# sumoboard.net
KiCad netlist of a schematic drawn in EAGLE
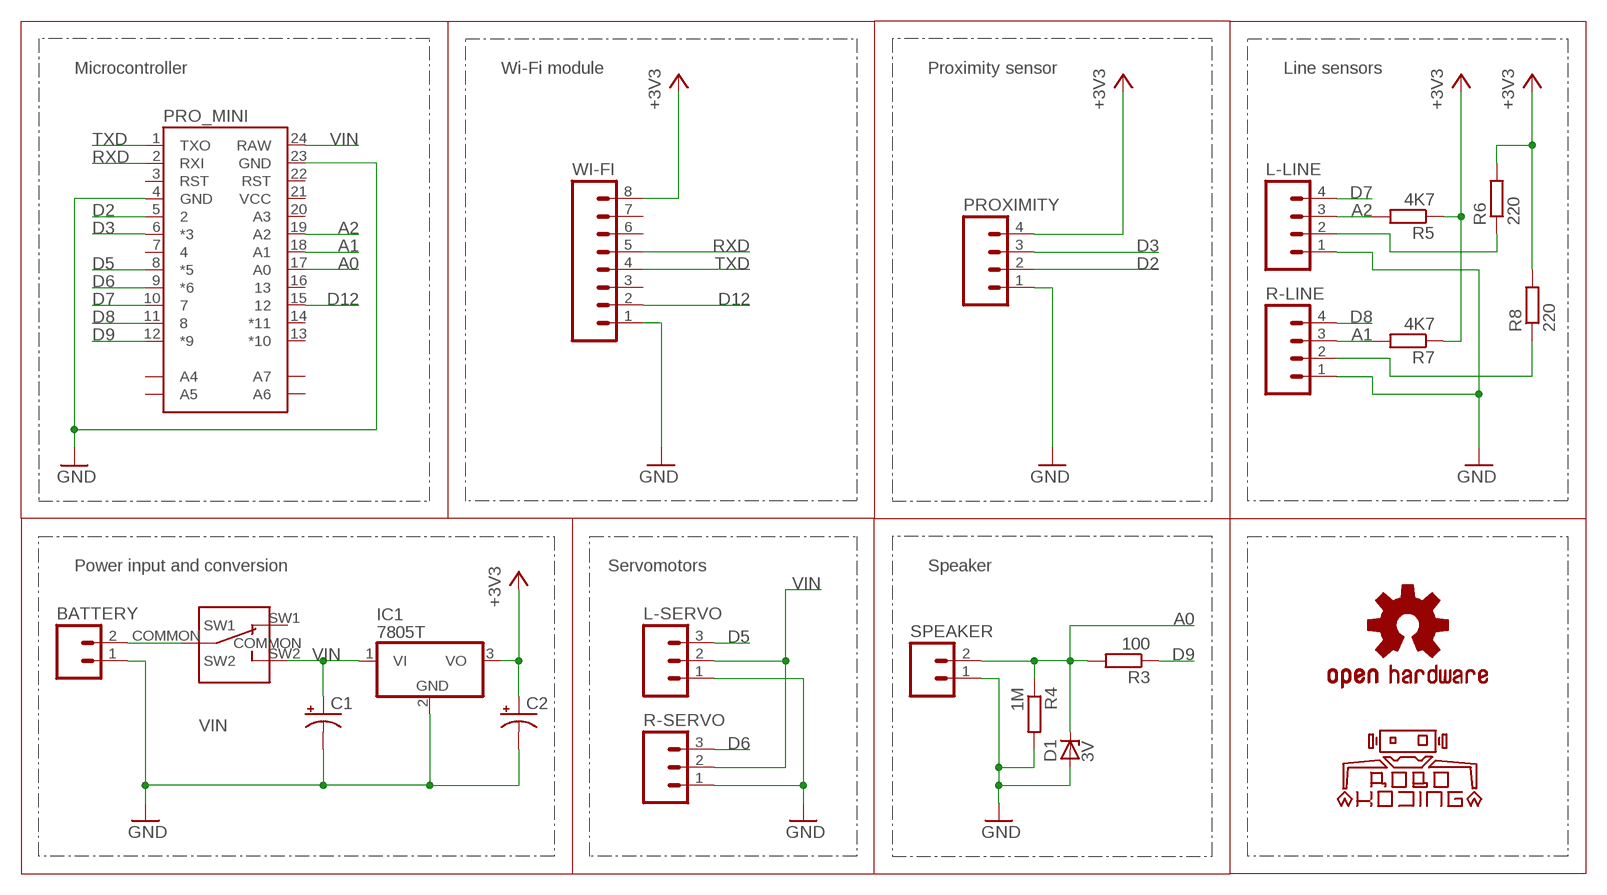
[diagram p0: schematic, sheet 1]

(export (version "E")
  (design (tool "Eeschema 10.0.6"))
  (components
    (comp (ref "BATTERY")
      (value "M02LOCK_LONGPADS")
      (footprint "eagle-import:1X02_LOCK_LONGPADS")
      (libsource (lib "eagle-import") (part "M02LOCK_LONGPADS"))
    )
    (comp (ref "C1")
      (value "CPOL-USE5-10.5")
      (footprint "eagle-import:E5-10,5")
      (libsource (lib "eagle-import") (part "CPOL-USE5-10.5"))
    )
    (comp (ref "C2")
      (value "CPOL-USE5-10.5")
      (footprint "eagle-import:E5-10,5")
      (libsource (lib "eagle-import") (part "CPOL-USE5-10.5"))
    )
    (comp (ref "D1")
      (value "3V")
      (footprint "eagle-import:DO35Z10")
      (libsource (lib "eagle-import") (part "1N821"))
    )
    (comp (ref "IC1")
      (value "7805T")
      (footprint "eagle-import:TO220H")
      (libsource (lib "eagle-import") (part "78T05"))
    )
    (comp (ref "L-LINE")
      (value "M04LOCK_LONGPADS")
      (footprint "eagle-import:1X04_LOCK_LONGPADS")
      (libsource (lib "eagle-import") (part "M04LOCK_LONGPADS"))
    )
    (comp (ref "L-SERVO")
      (value "M03LOCK_LONGPADS")
      (footprint "eagle-import:1X03_LOCK_LONGPADS")
      (libsource (lib "eagle-import") (part "M03LOCK_LONGPADS"))
    )
    (comp (ref "LOGO1")
      (value "OSHW-LOGOM")
      (footprint "eagle-import:OSHW-LOGO-M")
      (libsource (lib "eagle-import") (part "OSHW-LOGOM"))
    )
    (comp (ref "LOGO2")
      (value "ROBOKODING-LOGOM")
      (footprint "eagle-import:ROBOKODING-LOGO-M")
      (libsource (lib "eagle-import") (part "ROBOKODING-LOGOM"))
    )
    (comp (ref "POWER")
      (value "SPDT_SLIDE_SWITCH")
      (footprint "eagle-import:SPDT_SLIDE_SWITCH")
      (libsource (lib "eagle-import") (part "SPDT_SLIDE_SWITCH"))
    )
    (comp (ref "PROXIMITY")
      (value "M04LOCK_LONGPADS")
      (footprint "eagle-import:1X04_LOCK_LONGPADS")
      (libsource (lib "eagle-import") (part "M04LOCK_LONGPADS"))
    )
    (comp (ref "PRO_MINI")
      (value "ARDUINO_PRO_MINI")
      (footprint "eagle-import:ARDUINO_PRO_MINI")
      (libsource (lib "eagle-import") (part "ARDUINO_PRO_MINI"))
    )
    (comp (ref "R-LINE")
      (value "M04LOCK_LONGPADS")
      (footprint "eagle-import:1X04_LOCK_LONGPADS")
      (libsource (lib "eagle-import") (part "M04LOCK_LONGPADS"))
    )
    (comp (ref "R-SERVO")
      (value "M03LOCK_LONGPADS")
      (footprint "eagle-import:1X03_LOCK_LONGPADS")
      (libsource (lib "eagle-import") (part "M03LOCK_LONGPADS"))
    )
    (comp (ref "R3")
      (value "100")
      (footprint "eagle-import:0204_5")
      (libsource (lib "eagle-import") (part "R-EU_0204/5"))
    )
    (comp (ref "R4")
      (value "1M")
      (footprint "eagle-import:0204_5")
      (libsource (lib "eagle-import") (part "R-EU_0204/5"))
    )
    (comp (ref "R5")
      (value "4K7")
      (footprint "eagle-import:0204_5")
      (libsource (lib "eagle-import") (part "R-EU_0204/5"))
    )
    (comp (ref "R6")
      (value "220")
      (footprint "eagle-import:0204_5")
      (libsource (lib "eagle-import") (part "R-EU_0204/5"))
    )
    (comp (ref "R7")
      (value "4K7")
      (footprint "eagle-import:0204_5")
      (libsource (lib "eagle-import") (part "R-EU_0204/5"))
    )
    (comp (ref "R8")
      (value "220")
      (footprint "eagle-import:0204_5")
      (libsource (lib "eagle-import") (part "R-EU_0204/5"))
    )
    (comp (ref "SPEAKER")
      (value "M02LOCK_LONGPADS")
      (footprint "eagle-import:1X02_LOCK_LONGPADS")
      (libsource (lib "eagle-import") (part "M02LOCK_LONGPADS"))
    )
    (comp (ref "WI-FI")
      (value "M08LOCK_LONGPADS")
      (footprint "eagle-import:1X08_LOCK_LONGPADS")
      (libsource (lib "eagle-import") (part "M08LOCK_LONGPADS"))
    )
  )
  (nets
    (net (code "1") (name "+3V3") (class "Default")
      (node (ref "C2") (pin "+") (pinfunction "+_+") (pintype "passive"))
      (node (ref "IC1") (pin "3") (pinfunction "VO_3") (pintype "passive"))
      (node (ref "PROXIMITY") (pin "4") (pinfunction "4_4") (pintype "passive"))
      (node (ref "R5") (pin "1") (pinfunction "1_1") (pintype "passive"))
      (node (ref "R6") (pin "2") (pinfunction "2_2") (pintype "passive"))
      (node (ref "R7") (pin "1") (pinfunction "1_1") (pintype "passive"))
      (node (ref "R8") (pin "2") (pinfunction "2_2") (pintype "passive"))
      (node (ref "WI-FI") (pin "8") (pinfunction "8_8") (pintype "passive"))
    )
    (net (code "2") (name "/A0") (class "Default")
      (node (ref "D1") (pin "C") (pinfunction "C_C") (pintype "passive"))
      (node (ref "PRO_MINI") (pin "17") (pinfunction "A0_17") (pintype "bidirectional"))
      (node (ref "R3") (pin "2") (pinfunction "2_2") (pintype "passive"))
      (node (ref "R4") (pin "1") (pinfunction "1_1") (pintype "passive"))
      (node (ref "SPEAKER") (pin "2") (pinfunction "2_2") (pintype "passive"))
    )
    (net (code "3") (name "/A1") (class "Default")
      (node (ref "PRO_MINI") (pin "18") (pinfunction "A1_18") (pintype "bidirectional"))
      (node (ref "R-LINE") (pin "3") (pinfunction "3_3") (pintype "passive"))
      (node (ref "R7") (pin "2") (pinfunction "2_2") (pintype "passive"))
    )
    (net (code "4") (name "/A2") (class "Default")
      (node (ref "L-LINE") (pin "3") (pinfunction "3_3") (pintype "passive"))
      (node (ref "PRO_MINI") (pin "19") (pinfunction "A2_19") (pintype "bidirectional"))
      (node (ref "R5") (pin "2") (pinfunction "2_2") (pintype "passive"))
    )
    (net (code "5") (name "/D2") (class "Default")
      (node (ref "PROXIMITY") (pin "2") (pinfunction "2_2") (pintype "passive"))
      (node (ref "PRO_MINI") (pin "5") (pinfunction "2_5") (pintype "bidirectional"))
    )
    (net (code "6") (name "/D3") (class "Default")
      (node (ref "PROXIMITY") (pin "3") (pinfunction "3_3") (pintype "passive"))
      (node (ref "PRO_MINI") (pin "6") (pinfunction "*3_6") (pintype "bidirectional"))
    )
    (net (code "7") (name "/D5") (class "Default")
      (node (ref "L-SERVO") (pin "3") (pinfunction "3_3") (pintype "passive"))
      (node (ref "PRO_MINI") (pin "8") (pinfunction "*5_8") (pintype "bidirectional"))
    )
    (net (code "8") (name "/D6") (class "Default")
      (node (ref "PRO_MINI") (pin "9") (pinfunction "*6_9") (pintype "bidirectional"))
      (node (ref "R-SERVO") (pin "3") (pinfunction "3_3") (pintype "passive"))
    )
    (net (code "9") (name "/D7") (class "Default")
      (node (ref "L-LINE") (pin "4") (pinfunction "4_4") (pintype "passive"))
      (node (ref "PRO_MINI") (pin "10") (pinfunction "7_10") (pintype "bidirectional"))
    )
    (net (code "10") (name "/D8") (class "Default")
      (node (ref "PRO_MINI") (pin "11") (pinfunction "8_11") (pintype "bidirectional"))
      (node (ref "R-LINE") (pin "4") (pinfunction "4_4") (pintype "passive"))
    )
    (net (code "11") (name "/D9") (class "Default")
      (node (ref "PRO_MINI") (pin "12") (pinfunction "*9_12") (pintype "bidirectional"))
      (node (ref "R3") (pin "1") (pinfunction "1_1") (pintype "passive"))
    )
    (net (code "12") (name "/D12") (class "Default")
      (node (ref "PRO_MINI") (pin "15") (pinfunction "12_15") (pintype "bidirectional"))
      (node (ref "WI-FI") (pin "2") (pinfunction "2_2") (pintype "passive"))
    )
    (net (code "13") (name "/RXD") (class "Default")
      (node (ref "PRO_MINI") (pin "2") (pinfunction "RXI_2") (pintype "bidirectional"))
      (node (ref "WI-FI") (pin "5") (pinfunction "5_5") (pintype "passive"))
    )
    (net (code "14") (name "/TXD") (class "Default")
      (node (ref "PRO_MINI") (pin "1") (pinfunction "TXO_1") (pintype "bidirectional"))
      (node (ref "WI-FI") (pin "4") (pinfunction "4_4") (pintype "passive"))
    )
    (net (code "15") (name "/VIN") (class "Default")
      (node (ref "C1") (pin "+") (pinfunction "+_+") (pintype "passive"))
      (node (ref "IC1") (pin "1") (pinfunction "VI_1") (pintype "input"))
      (node (ref "L-SERVO") (pin "2") (pinfunction "2_2") (pintype "passive"))
      (node (ref "POWER") (pin "SW2") (pinfunction "SW2_SW2") (pintype "bidirectional"))
      (node (ref "PRO_MINI") (pin "24") (pinfunction "RAW_24") (pintype "bidirectional"))
      (node (ref "R-SERVO") (pin "2") (pinfunction "2_2") (pintype "passive"))
    )
    (net (code "16") (name "GND") (class "Default")
      (node (ref "BATTERY") (pin "1") (pinfunction "1_1") (pintype "passive"))
      (node (ref "C1") (pin "-") (pinfunction "-_-") (pintype "passive"))
      (node (ref "C2") (pin "-") (pinfunction "-_-") (pintype "passive"))
      (node (ref "D1") (pin "A") (pinfunction "A_A") (pintype "passive"))
      (node (ref "IC1") (pin "2") (pinfunction "GND_2") (pintype "passive"))
      (node (ref "L-LINE") (pin "1") (pinfunction "1_1") (pintype "passive"))
      (node (ref "L-SERVO") (pin "1") (pinfunction "1_1") (pintype "passive"))
      (node (ref "PROXIMITY") (pin "1") (pinfunction "1_1") (pintype "passive"))
      (node (ref "PRO_MINI") (pin "23") (pinfunction "GND_23") (pintype "bidirectional"))
      (node (ref "PRO_MINI") (pin "4") (pinfunction "GND_4") (pintype "bidirectional"))
      (node (ref "R-LINE") (pin "1") (pinfunction "1_1") (pintype "passive"))
      (node (ref "R-SERVO") (pin "1") (pinfunction "1_1") (pintype "passive"))
      (node (ref "R4") (pin "2") (pinfunction "2_2") (pintype "passive"))
      (node (ref "SPEAKER") (pin "1") (pinfunction "1_1") (pintype "passive"))
      (node (ref "WI-FI") (pin "1") (pinfunction "1_1") (pintype "passive"))
    )
    (net (code "17") (name "Net-(BATTERY-Pad2)") (class "Default")
      (node (ref "BATTERY") (pin "2") (pinfunction "2_2") (pintype "passive"))
      (node (ref "POWER") (pin "COMMON") (pinfunction "COMMON_COMMON") (pintype "bidirectional"))
    )
    (net (code "18") (name "Net-(L-LINE-Pad2)") (class "Default")
      (node (ref "L-LINE") (pin "2") (pinfunction "2_2") (pintype "passive"))
      (node (ref "R6") (pin "1") (pinfunction "1_1") (pintype "passive"))
    )
    (net (code "19") (name "Net-(R-LINE-Pad2)") (class "Default")
      (node (ref "R-LINE") (pin "2") (pinfunction "2_2") (pintype "passive"))
      (node (ref "R8") (pin "1") (pinfunction "1_1") (pintype "passive"))
    )
    (net (code "20") (name "unconnected-(POWER-PadSW1)") (class "Default")
      (node (ref "POWER") (pin "SW1") (pinfunction "SW1_SW1") (pintype "bidirectional"))
    )
    (net (code "21") (name "unconnected-(PRO_MINI-*10-Pad13)") (class "Default")
      (node (ref "PRO_MINI") (pin "13") (pinfunction "*10_13") (pintype "bidirectional"))
    )
    (net (code "22") (name "unconnected-(PRO_MINI-*11-Pad14)") (class "Default")
      (node (ref "PRO_MINI") (pin "14") (pinfunction "*11_14") (pintype "bidirectional"))
    )
    (net (code "23") (name "unconnected-(PRO_MINI-4-Pad7)") (class "Default")
      (node (ref "PRO_MINI") (pin "7") (pinfunction "4_7") (pintype "bidirectional"))
    )
    (net (code "24") (name "unconnected-(PRO_MINI-13-Pad16)") (class "Default")
      (node (ref "PRO_MINI") (pin "16") (pinfunction "13_16") (pintype "bidirectional"))
    )
    (net (code "25") (name "unconnected-(PRO_MINI-A3-Pad20)") (class "Default")
      (node (ref "PRO_MINI") (pin "20") (pinfunction "A3_20") (pintype "bidirectional"))
    )
    (net (code "26") (name "unconnected-(PRO_MINI-RST-Pad3)") (class "Default")
      (node (ref "PRO_MINI") (pin "3") (pinfunction "RST_3") (pintype "bidirectional"))
    )
    (net (code "27") (name "unconnected-(PRO_MINI-RST-Pad22)") (class "Default")
      (node (ref "PRO_MINI") (pin "22") (pinfunction "RST_22") (pintype "bidirectional"))
    )
    (net (code "28") (name "unconnected-(PRO_MINI-VCC-Pad21)") (class "Default")
      (node (ref "PRO_MINI") (pin "21") (pinfunction "VCC_21") (pintype "bidirectional"))
    )
    (net (code "29") (name "unconnected-(WI-FI-Pad3)") (class "Default")
      (node (ref "WI-FI") (pin "3") (pinfunction "3_3") (pintype "passive"))
    )
    (net (code "30") (name "unconnected-(WI-FI-Pad6)") (class "Default")
      (node (ref "WI-FI") (pin "6") (pinfunction "6_6") (pintype "passive"))
    )
    (net (code "31") (name "unconnected-(WI-FI-Pad7)") (class "Default")
      (node (ref "WI-FI") (pin "7") (pinfunction "7_7") (pintype "passive"))
    )
  )
)
